# Steering_Wheel_Raspberry_Pi.net
KiCad netlist of a schematic drawn in EAGLE
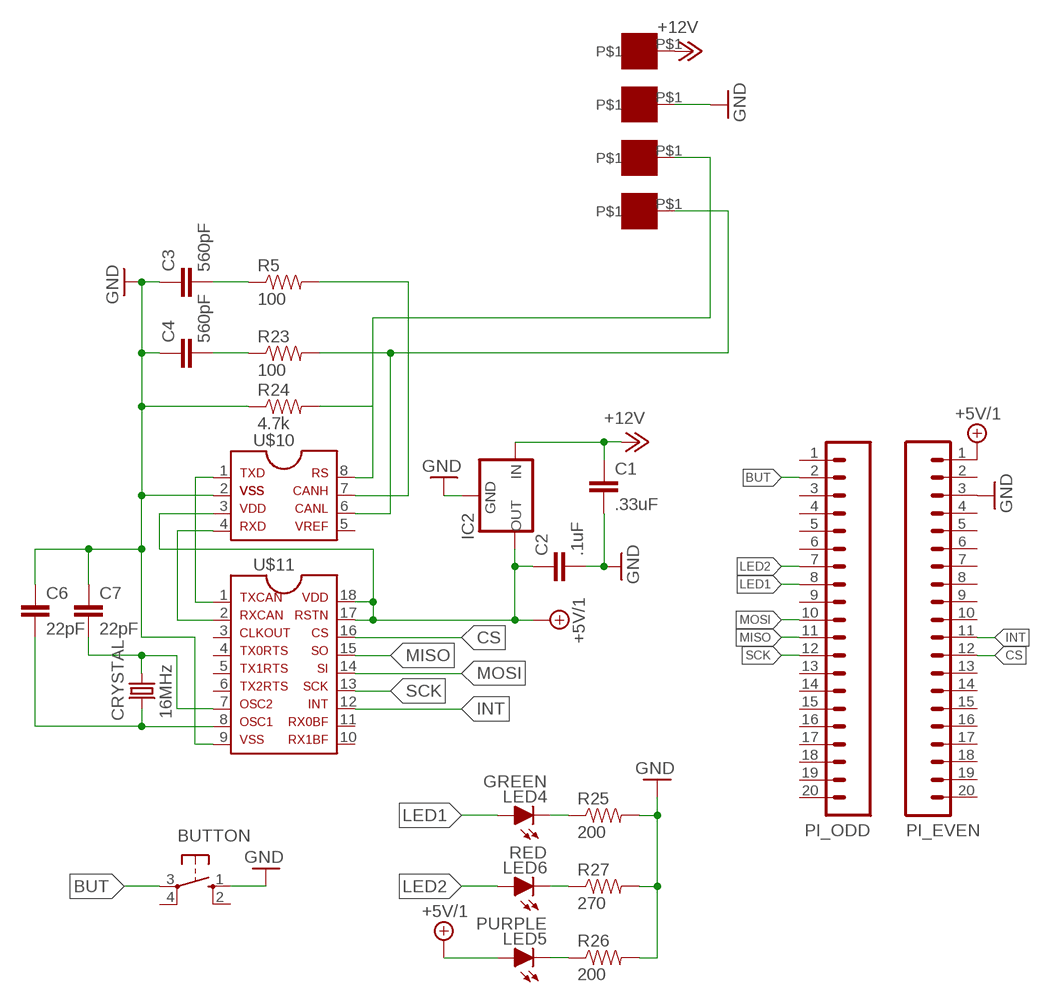
[diagram p0: schematic, sheet 1]

(export (version "E")
  (design (tool "Eeschema 10.0.6"))
  (components
    (comp (ref "BUTTON")
      (value "BTN_10-XX")
      (footprint "eagle-import:B3F-10XX")
      (fields (field (name "MPN") "B3F-1000"))
      (libsource (lib "eagle-import") (part "BTN_10-XX"))
    )
    (comp (ref "C1")
      (value ".33uF")
      (footprint "eagle-import:0805")
      (libsource (lib "eagle-import") (part "CAP0805"))
    )
    (comp (ref "C2")
      (value ".1uF")
      (footprint "eagle-import:0805")
      (libsource (lib "eagle-import") (part "CAP0805"))
    )
    (comp (ref "C3")
      (value "560pF")
      (footprint "eagle-import:0805")
      (libsource (lib "eagle-import") (part "CAP0805"))
    )
    (comp (ref "C4")
      (value "560pF")
      (footprint "eagle-import:0805")
      (libsource (lib "eagle-import") (part "CAP0805"))
    )
    (comp (ref "C6")
      (value "22pF")
      (footprint "eagle-import:0805")
      (libsource (lib "eagle-import") (part "CAP0805"))
    )
    (comp (ref "C7")
      (value "22pF")
      (footprint "eagle-import:0805")
      (libsource (lib "eagle-import") (part "CAP0805"))
    )
    (comp (ref "CRYSTAL")
      (value "16MHz")
      (footprint "eagle-import:HC49UP")
      (libsource (lib "eagle-import") (part "CRYSTALSMD"))
    )
    (comp (ref "IC2")
      (value "OKI-78SR-5/1.5-W36-C_VERT")
      (footprint "eagle-import:TO-220")
      (libsource (lib "eagle-import") (part "OKI-78SR-5/1.5-W36-C_VERT"))
    )
    (comp (ref "LED4")
      (value "GREEN")
      (footprint "eagle-import:LED-805")
      (libsource (lib "eagle-import") (part "LED-0805"))
    )
    (comp (ref "LED5")
      (value "PURPLE")
      (footprint "eagle-import:LED-805")
      (libsource (lib "eagle-import") (part "LED-0805"))
    )
    (comp (ref "LED6")
      (value "RED")
      (footprint "eagle-import:LED-805")
      (libsource (lib "eagle-import") (part "LED-0805"))
    )
    (comp (ref "PI_EVEN")
      (value "M20")
      (footprint "eagle-import:1X20")
      (libsource (lib "eagle-import") (part "M20"))
    )
    (comp (ref "PI_ODD")
      (value "M20")
      (footprint "eagle-import:1X20")
      (libsource (lib "eagle-import") (part "M20"))
    )
    (comp (ref "R5")
      (value "100")
      (footprint "eagle-import:0805")
      (libsource (lib "eagle-import") (part "RESISTOR0805-RES"))
    )
    (comp (ref "R23")
      (value "100")
      (footprint "eagle-import:0805")
      (libsource (lib "eagle-import") (part "RESISTOR0805-RES"))
    )
    (comp (ref "R24")
      (value "4.7k")
      (footprint "eagle-import:0805")
      (libsource (lib "eagle-import") (part "RESISTOR0805-RES"))
    )
    (comp (ref "R25")
      (value "200")
      (footprint "eagle-import:0805")
      (libsource (lib "eagle-import") (part "RESISTOR0805-RES"))
    )
    (comp (ref "R26")
      (value "200")
      (footprint "eagle-import:0805")
      (libsource (lib "eagle-import") (part "RESISTOR0805-RES"))
    )
    (comp (ref "R27")
      (value "270")
      (footprint "eagle-import:0805")
      (libsource (lib "eagle-import") (part "RESISTOR0805-RES"))
    )
    (comp (ref "U$1")
      (value "SOLDER_PAD")
      (footprint "eagle-import:SOLDER_PAD_XSMALL")
      (libsource (lib "eagle-import") (part "SOLDER_PAD"))
    )
    (comp (ref "U$2")
      (value "SOLDER_PAD")
      (footprint "eagle-import:SOLDER_PAD_XSMALL")
      (libsource (lib "eagle-import") (part "SOLDER_PAD"))
    )
    (comp (ref "U$3")
      (value "SOLDER_PAD")
      (footprint "eagle-import:SOLDER_PAD_XSMALL")
      (libsource (lib "eagle-import") (part "SOLDER_PAD"))
    )
    (comp (ref "U$4")
      (value "SOLDER_PAD")
      (footprint "eagle-import:SOLDER_PAD_XSMALL")
      (libsource (lib "eagle-import") (part "SOLDER_PAD"))
    )
    (comp (ref "U$10")
      (value "MCP2551")
      (footprint "eagle-import:SOIC-08")
      (libsource (lib "eagle-import") (part "MCP2551"))
    )
    (comp (ref "U$11")
      (value "MCP2515SMD")
      (footprint "eagle-import:SOIC-18W")
      (libsource (lib "eagle-import") (part "MCP2515SMD"))
    )
  )
  (nets
    (net (code "1") (name "+5V{slash}1") (class "Default")
      (node (ref "C2") (pin "1") (pinfunction "1_1") (pintype "passive"))
      (node (ref "IC2") (pin "3") (pinfunction "OUT_3") (pintype "output"))
      (node (ref "LED5") (pin "A") (pinfunction "A_A") (pintype "passive"))
      (node (ref "PI_EVEN") (pin "1") (pinfunction "1_1") (pintype "passive"))
      (node (ref "U$10") (pin "3") (pinfunction "3_3") (pintype "passive"))
      (node (ref "U$11") (pin "17") (pinfunction "17_17") (pintype "passive"))
      (node (ref "U$11") (pin "18") (pinfunction "18_18") (pintype "passive"))
    )
    (net (code "2") (name "+12V") (class "Default")
      (node (ref "C1") (pin "1") (pinfunction "1_1") (pintype "passive"))
      (node (ref "IC2") (pin "1") (pinfunction "IN_1") (pintype "input"))
      (node (ref "U$1") (pin "P$1") (pinfunction "P$1_P$1") (pintype "bidirectional"))
    )
    (net (code "3") (name "BUT") (class "Default")
      (node (ref "BUTTON") (pin "3") (pinfunction "P_3") (pintype "passive"))
      (node (ref "PI_ODD") (pin "2") (pinfunction "2_2") (pintype "passive"))
    )
    (net (code "4") (name "CS") (class "Default")
      (node (ref "PI_EVEN") (pin "12") (pinfunction "12_12") (pintype "passive"))
      (node (ref "U$11") (pin "16") (pinfunction "16_16") (pintype "passive"))
    )
    (net (code "5") (name "GND") (class "Default")
      (node (ref "BUTTON") (pin "1") (pinfunction "S_1") (pintype "passive"))
      (node (ref "C1") (pin "2") (pinfunction "2_2") (pintype "passive"))
      (node (ref "C2") (pin "2") (pinfunction "2_2") (pintype "passive"))
      (node (ref "C3") (pin "1") (pinfunction "1_1") (pintype "passive"))
      (node (ref "C4") (pin "1") (pinfunction "1_1") (pintype "passive"))
      (node (ref "C6") (pin "1") (pinfunction "1_1") (pintype "passive"))
      (node (ref "C7") (pin "1") (pinfunction "1_1") (pintype "passive"))
      (node (ref "IC2") (pin "2") (pinfunction "GND_2") (pintype "input"))
      (node (ref "PI_EVEN") (pin "3") (pinfunction "3_3") (pintype "passive"))
      (node (ref "R24") (pin "1") (pinfunction "1_1") (pintype "passive"))
      (node (ref "R25") (pin "2") (pinfunction "2_2") (pintype "passive"))
      (node (ref "R26") (pin "2") (pinfunction "2_2") (pintype "passive"))
      (node (ref "R27") (pin "2") (pinfunction "2_2") (pintype "passive"))
      (node (ref "U$10") (pin "2") (pinfunction "2_2") (pintype "passive"))
      (node (ref "U$11") (pin "9") (pinfunction "9_9") (pintype "passive"))
      (node (ref "U$2") (pin "P$1") (pinfunction "P$1_P$1") (pintype "bidirectional"))
    )
    (net (code "6") (name "INT") (class "Default")
      (node (ref "PI_EVEN") (pin "11") (pinfunction "11_11") (pintype "passive"))
      (node (ref "U$11") (pin "12") (pinfunction "12_12") (pintype "passive"))
    )
    (net (code "7") (name "LED1") (class "Default")
      (node (ref "LED4") (pin "A") (pinfunction "A_A") (pintype "passive"))
      (node (ref "PI_ODD") (pin "8") (pinfunction "8_8") (pintype "passive"))
    )
    (net (code "8") (name "LED2") (class "Default")
      (node (ref "LED6") (pin "A") (pinfunction "A_A") (pintype "passive"))
      (node (ref "PI_ODD") (pin "7") (pinfunction "7_7") (pintype "passive"))
    )
    (net (code "9") (name "MISO") (class "Default")
      (node (ref "PI_ODD") (pin "11") (pinfunction "11_11") (pintype "passive"))
      (node (ref "U$11") (pin "15") (pinfunction "15_15") (pintype "passive"))
    )
    (net (code "10") (name "MOSI") (class "Default")
      (node (ref "PI_ODD") (pin "10") (pinfunction "10_10") (pintype "passive"))
      (node (ref "U$11") (pin "14") (pinfunction "14_14") (pintype "passive"))
    )
    (net (code "11") (name "Net-(C3-Pad2)") (class "Default")
      (node (ref "C3") (pin "2") (pinfunction "2_2") (pintype "passive"))
      (node (ref "R5") (pin "1") (pinfunction "1_1") (pintype "passive"))
    )
    (net (code "12") (name "Net-(C4-Pad2)") (class "Default")
      (node (ref "C4") (pin "2") (pinfunction "2_2") (pintype "passive"))
      (node (ref "R23") (pin "1") (pinfunction "1_1") (pintype "passive"))
    )
    (net (code "13") (name "Net-(C6-Pad2)") (class "Default")
      (node (ref "C6") (pin "2") (pinfunction "2_2") (pintype "passive"))
      (node (ref "CRYSTAL") (pin "2") (pinfunction "2_2") (pintype "passive"))
      (node (ref "U$11") (pin "8") (pinfunction "8_8") (pintype "passive"))
    )
    (net (code "14") (name "Net-(C7-Pad2)") (class "Default")
      (node (ref "C7") (pin "2") (pinfunction "2_2") (pintype "passive"))
      (node (ref "CRYSTAL") (pin "1") (pinfunction "1_1") (pintype "passive"))
      (node (ref "U$11") (pin "7") (pinfunction "7_7") (pintype "passive"))
    )
    (net (code "15") (name "Net-(LED4-PadC)") (class "Default")
      (node (ref "LED4") (pin "C") (pinfunction "C_C") (pintype "passive"))
      (node (ref "R25") (pin "1") (pinfunction "1_1") (pintype "passive"))
    )
    (net (code "16") (name "Net-(LED5-PadC)") (class "Default")
      (node (ref "LED5") (pin "C") (pinfunction "C_C") (pintype "passive"))
      (node (ref "R26") (pin "1") (pinfunction "1_1") (pintype "passive"))
    )
    (net (code "17") (name "Net-(LED6-PadC)") (class "Default")
      (node (ref "LED6") (pin "C") (pinfunction "C_C") (pintype "passive"))
      (node (ref "R27") (pin "1") (pinfunction "1_1") (pintype "passive"))
    )
    (net (code "18") (name "Net-(R5-Pad2)") (class "Default")
      (node (ref "R5") (pin "2") (pinfunction "2_2") (pintype "passive"))
      (node (ref "U$10") (pin "7") (pinfunction "7_7") (pintype "passive"))
    )
    (net (code "19") (name "Net-(R23-Pad2)") (class "Default")
      (node (ref "R23") (pin "2") (pinfunction "2_2") (pintype "passive"))
      (node (ref "U$10") (pin "6") (pinfunction "6_6") (pintype "passive"))
      (node (ref "U$4") (pin "P$1") (pinfunction "P$1_P$1") (pintype "bidirectional"))
    )
    (net (code "20") (name "Net-(R24-Pad2)") (class "Default")
      (node (ref "R24") (pin "2") (pinfunction "2_2") (pintype "passive"))
      (node (ref "U$10") (pin "8") (pinfunction "8_8") (pintype "passive"))
      (node (ref "U$3") (pin "P$1") (pinfunction "P$1_P$1") (pintype "bidirectional"))
    )
    (net (code "21") (name "Net-(U$10-Pad1)") (class "Default")
      (node (ref "U$10") (pin "1") (pinfunction "1_1") (pintype "passive"))
      (node (ref "U$11") (pin "1") (pinfunction "1_1") (pintype "passive"))
    )
    (net (code "22") (name "Net-(U$10-Pad4)") (class "Default")
      (node (ref "U$10") (pin "4") (pinfunction "4_4") (pintype "passive"))
      (node (ref "U$11") (pin "2") (pinfunction "2_2") (pintype "passive"))
    )
    (net (code "23") (name "SCK") (class "Default")
      (node (ref "PI_ODD") (pin "12") (pinfunction "12_12") (pintype "passive"))
      (node (ref "U$11") (pin "13") (pinfunction "13_13") (pintype "passive"))
    )
    (net (code "24") (name "unconnected-(BUTTON-P1-Pad4)") (class "Default")
      (node (ref "BUTTON") (pin "4") (pinfunction "P1_4") (pintype "passive"))
    )
    (net (code "25") (name "unconnected-(BUTTON-S1-Pad2)") (class "Default")
      (node (ref "BUTTON") (pin "2") (pinfunction "S1_2") (pintype "passive"))
    )
    (net (code "26") (name "unconnected-(PI_EVEN-Pad2)") (class "Default")
      (node (ref "PI_EVEN") (pin "2") (pinfunction "2_2") (pintype "passive"))
    )
    (net (code "27") (name "unconnected-(PI_EVEN-Pad4)") (class "Default")
      (node (ref "PI_EVEN") (pin "4") (pinfunction "4_4") (pintype "passive"))
    )
    (net (code "28") (name "unconnected-(PI_EVEN-Pad5)") (class "Default")
      (node (ref "PI_EVEN") (pin "5") (pinfunction "5_5") (pintype "passive"))
    )
    (net (code "29") (name "unconnected-(PI_EVEN-Pad6)") (class "Default")
      (node (ref "PI_EVEN") (pin "6") (pinfunction "6_6") (pintype "passive"))
    )
    (net (code "30") (name "unconnected-(PI_EVEN-Pad7)") (class "Default")
      (node (ref "PI_EVEN") (pin "7") (pinfunction "7_7") (pintype "passive"))
    )
    (net (code "31") (name "unconnected-(PI_EVEN-Pad8)") (class "Default")
      (node (ref "PI_EVEN") (pin "8") (pinfunction "8_8") (pintype "passive"))
    )
    (net (code "32") (name "unconnected-(PI_EVEN-Pad9)") (class "Default")
      (node (ref "PI_EVEN") (pin "9") (pinfunction "9_9") (pintype "passive"))
    )
    (net (code "33") (name "unconnected-(PI_EVEN-Pad10)") (class "Default")
      (node (ref "PI_EVEN") (pin "10") (pinfunction "10_10") (pintype "passive"))
    )
    (net (code "34") (name "unconnected-(PI_EVEN-Pad13)") (class "Default")
      (node (ref "PI_EVEN") (pin "13") (pinfunction "13_13") (pintype "passive"))
    )
    (net (code "35") (name "unconnected-(PI_EVEN-Pad14)") (class "Default")
      (node (ref "PI_EVEN") (pin "14") (pinfunction "14_14") (pintype "passive"))
    )
    (net (code "36") (name "unconnected-(PI_EVEN-Pad15)") (class "Default")
      (node (ref "PI_EVEN") (pin "15") (pinfunction "15_15") (pintype "passive"))
    )
    (net (code "37") (name "unconnected-(PI_EVEN-Pad16)") (class "Default")
      (node (ref "PI_EVEN") (pin "16") (pinfunction "16_16") (pintype "passive"))
    )
    (net (code "38") (name "unconnected-(PI_EVEN-Pad17)") (class "Default")
      (node (ref "PI_EVEN") (pin "17") (pinfunction "17_17") (pintype "passive"))
    )
    (net (code "39") (name "unconnected-(PI_EVEN-Pad18)") (class "Default")
      (node (ref "PI_EVEN") (pin "18") (pinfunction "18_18") (pintype "passive"))
    )
    (net (code "40") (name "unconnected-(PI_EVEN-Pad19)") (class "Default")
      (node (ref "PI_EVEN") (pin "19") (pinfunction "19_19") (pintype "passive"))
    )
    (net (code "41") (name "unconnected-(PI_EVEN-Pad20)") (class "Default")
      (node (ref "PI_EVEN") (pin "20") (pinfunction "20_20") (pintype "passive"))
    )
    (net (code "42") (name "unconnected-(PI_ODD-Pad1)") (class "Default")
      (node (ref "PI_ODD") (pin "1") (pinfunction "1_1") (pintype "passive"))
    )
    (net (code "43") (name "unconnected-(PI_ODD-Pad3)") (class "Default")
      (node (ref "PI_ODD") (pin "3") (pinfunction "3_3") (pintype "passive"))
    )
    (net (code "44") (name "unconnected-(PI_ODD-Pad4)") (class "Default")
      (node (ref "PI_ODD") (pin "4") (pinfunction "4_4") (pintype "passive"))
    )
    (net (code "45") (name "unconnected-(PI_ODD-Pad5)") (class "Default")
      (node (ref "PI_ODD") (pin "5") (pinfunction "5_5") (pintype "passive"))
    )
    (net (code "46") (name "unconnected-(PI_ODD-Pad6)") (class "Default")
      (node (ref "PI_ODD") (pin "6") (pinfunction "6_6") (pintype "passive"))
    )
    (net (code "47") (name "unconnected-(PI_ODD-Pad9)") (class "Default")
      (node (ref "PI_ODD") (pin "9") (pinfunction "9_9") (pintype "passive"))
    )
    (net (code "48") (name "unconnected-(PI_ODD-Pad13)") (class "Default")
      (node (ref "PI_ODD") (pin "13") (pinfunction "13_13") (pintype "passive"))
    )
    (net (code "49") (name "unconnected-(PI_ODD-Pad14)") (class "Default")
      (node (ref "PI_ODD") (pin "14") (pinfunction "14_14") (pintype "passive"))
    )
    (net (code "50") (name "unconnected-(PI_ODD-Pad15)") (class "Default")
      (node (ref "PI_ODD") (pin "15") (pinfunction "15_15") (pintype "passive"))
    )
    (net (code "51") (name "unconnected-(PI_ODD-Pad16)") (class "Default")
      (node (ref "PI_ODD") (pin "16") (pinfunction "16_16") (pintype "passive"))
    )
    (net (code "52") (name "unconnected-(PI_ODD-Pad17)") (class "Default")
      (node (ref "PI_ODD") (pin "17") (pinfunction "17_17") (pintype "passive"))
    )
    (net (code "53") (name "unconnected-(PI_ODD-Pad18)") (class "Default")
      (node (ref "PI_ODD") (pin "18") (pinfunction "18_18") (pintype "passive"))
    )
    (net (code "54") (name "unconnected-(PI_ODD-Pad19)") (class "Default")
      (node (ref "PI_ODD") (pin "19") (pinfunction "19_19") (pintype "passive"))
    )
    (net (code "55") (name "unconnected-(PI_ODD-Pad20)") (class "Default")
      (node (ref "PI_ODD") (pin "20") (pinfunction "20_20") (pintype "passive"))
    )
    (net (code "56") (name "unconnected-(U$10-Pad5)") (class "Default")
      (node (ref "U$10") (pin "5") (pinfunction "5_5") (pintype "passive"))
    )
    (net (code "57") (name "unconnected-(U$11-Pad3)") (class "Default")
      (node (ref "U$11") (pin "3") (pinfunction "3_3") (pintype "passive"))
    )
    (net (code "58") (name "unconnected-(U$11-Pad4)") (class "Default")
      (node (ref "U$11") (pin "4") (pinfunction "4_4") (pintype "passive"))
    )
    (net (code "59") (name "unconnected-(U$11-Pad5)") (class "Default")
      (node (ref "U$11") (pin "5") (pinfunction "5_5") (pintype "passive"))
    )
    (net (code "60") (name "unconnected-(U$11-Pad6)") (class "Default")
      (node (ref "U$11") (pin "6") (pinfunction "6_6") (pintype "passive"))
    )
    (net (code "61") (name "unconnected-(U$11-Pad10)") (class "Default")
      (node (ref "U$11") (pin "10") (pinfunction "10_10") (pintype "passive"))
    )
    (net (code "62") (name "unconnected-(U$11-Pad11)") (class "Default")
      (node (ref "U$11") (pin "11") (pinfunction "11_11") (pintype "passive"))
    )
  )
)
